# Presencia_Agua.net
KiCad netlist of a schematic drawn in Altium Designer
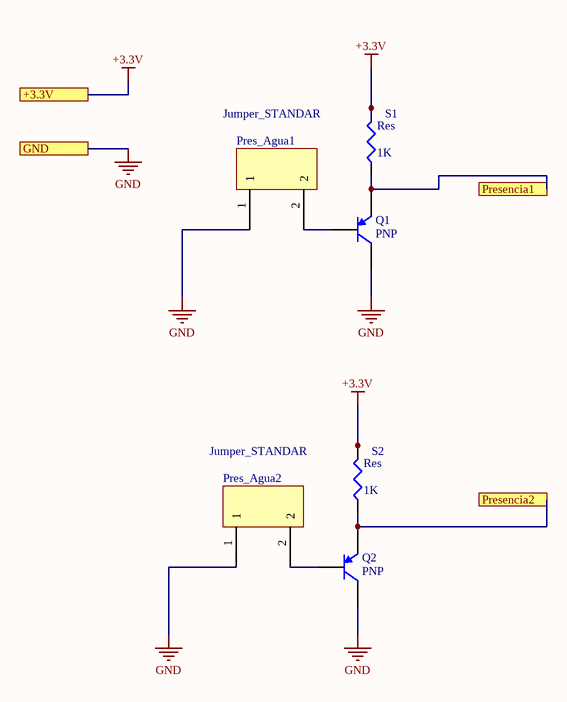
[diagram p0: Presencia_Agua.SchDoc]

(export (version "E")
  (design (tool "Eeschema 10.0.6"))
  (components
    (comp (ref "Pres_Agua1")
      (value "Jumper_STANDAR")
      (footprint "HDR1X2H")
      (libsource (lib "XSUB_COMP") (part "Jumper_STANDAR"))
    )
    (comp (ref "Pres_Agua2")
      (value "Jumper_STANDAR")
      (footprint "HDR1X2H")
      (libsource (lib "XSUB_COMP") (part "Jumper_STANDAR"))
    )
    (comp (ref "Q1")
      (value "PNP")
      (footprint "SOT-23B_L")
      (description "PNP Bipolar Transistor")
      (fields (field (name "PUBLISHER") "Altium Limited"))
      (libsource (lib "Miscellaneous Devices") (part "PNP"))
    )
    (comp (ref "Q2")
      (value "PNP")
      (footprint "SOT-23B_L")
      (description "PNP Bipolar Transistor")
      (fields (field (name "PUBLISHER") "Altium Limited"))
      (libsource (lib "Miscellaneous Devices") (part "PNP"))
    )
    (comp (ref "S1")
      (value "Res")
      (footprint "RESC6332")
      (description "Resistor")
      (fields (field (name "ALTIUM_VALUE") "1K") (field (name "PUBLISHER") "Altium Limited"))
      (libsource (lib "Miscellaneous Devices") (part "Res3"))
    )
    (comp (ref "S2")
      (value "Res")
      (footprint "RESC6332")
      (description "Resistor")
      (fields (field (name "ALTIUM_VALUE") "1K") (field (name "PUBLISHER") "Altium Limited"))
      (libsource (lib "Miscellaneous Devices") (part "Res3"))
    )
  )
  (nets
    (net (code "1") (name "+3.3V") (class "Default")
      (node (ref "S1") (pin "2") (pinfunction "2_2") (pintype "passive"))
      (node (ref "S2") (pin "2") (pinfunction "2_2") (pintype "passive"))
    )
    (net (code "2") (name "/Presencia1") (class "Default")
      (node (ref "Q1") (pin "3") (pinfunction "E_3") (pintype "passive"))
      (node (ref "S1") (pin "1") (pinfunction "1_1") (pintype "passive"))
    )
    (net (code "3") (name "/Presencia2") (class "Default")
      (node (ref "Q2") (pin "3") (pinfunction "E_3") (pintype "passive"))
      (node (ref "S2") (pin "1") (pinfunction "1_1") (pintype "passive"))
    )
    (net (code "4") (name "GND") (class "Default")
      (node (ref "Pres_Agua1") (pin "1") (pinfunction "1_1") (pintype "passive"))
      (node (ref "Pres_Agua2") (pin "1") (pinfunction "1_1") (pintype "passive"))
      (node (ref "Q1") (pin "1") (pinfunction "C_1") (pintype "passive"))
      (node (ref "Q2") (pin "1") (pinfunction "C_1") (pintype "passive"))
    )
    (net (code "5") (name "Net-(Q1-B)") (class "Default")
      (node (ref "Pres_Agua1") (pin "2") (pinfunction "2_2") (pintype "passive"))
      (node (ref "Q1") (pin "2") (pinfunction "B_2") (pintype "passive"))
    )
    (net (code "6") (name "Net-(Q2-B)") (class "Default")
      (node (ref "Pres_Agua2") (pin "2") (pinfunction "2_2") (pintype "passive"))
      (node (ref "Q2") (pin "2") (pinfunction "B_2") (pintype "passive"))
    )
  )
)
